# ruler.net
KiCad netlist of a schematic drawn in Altium Designer
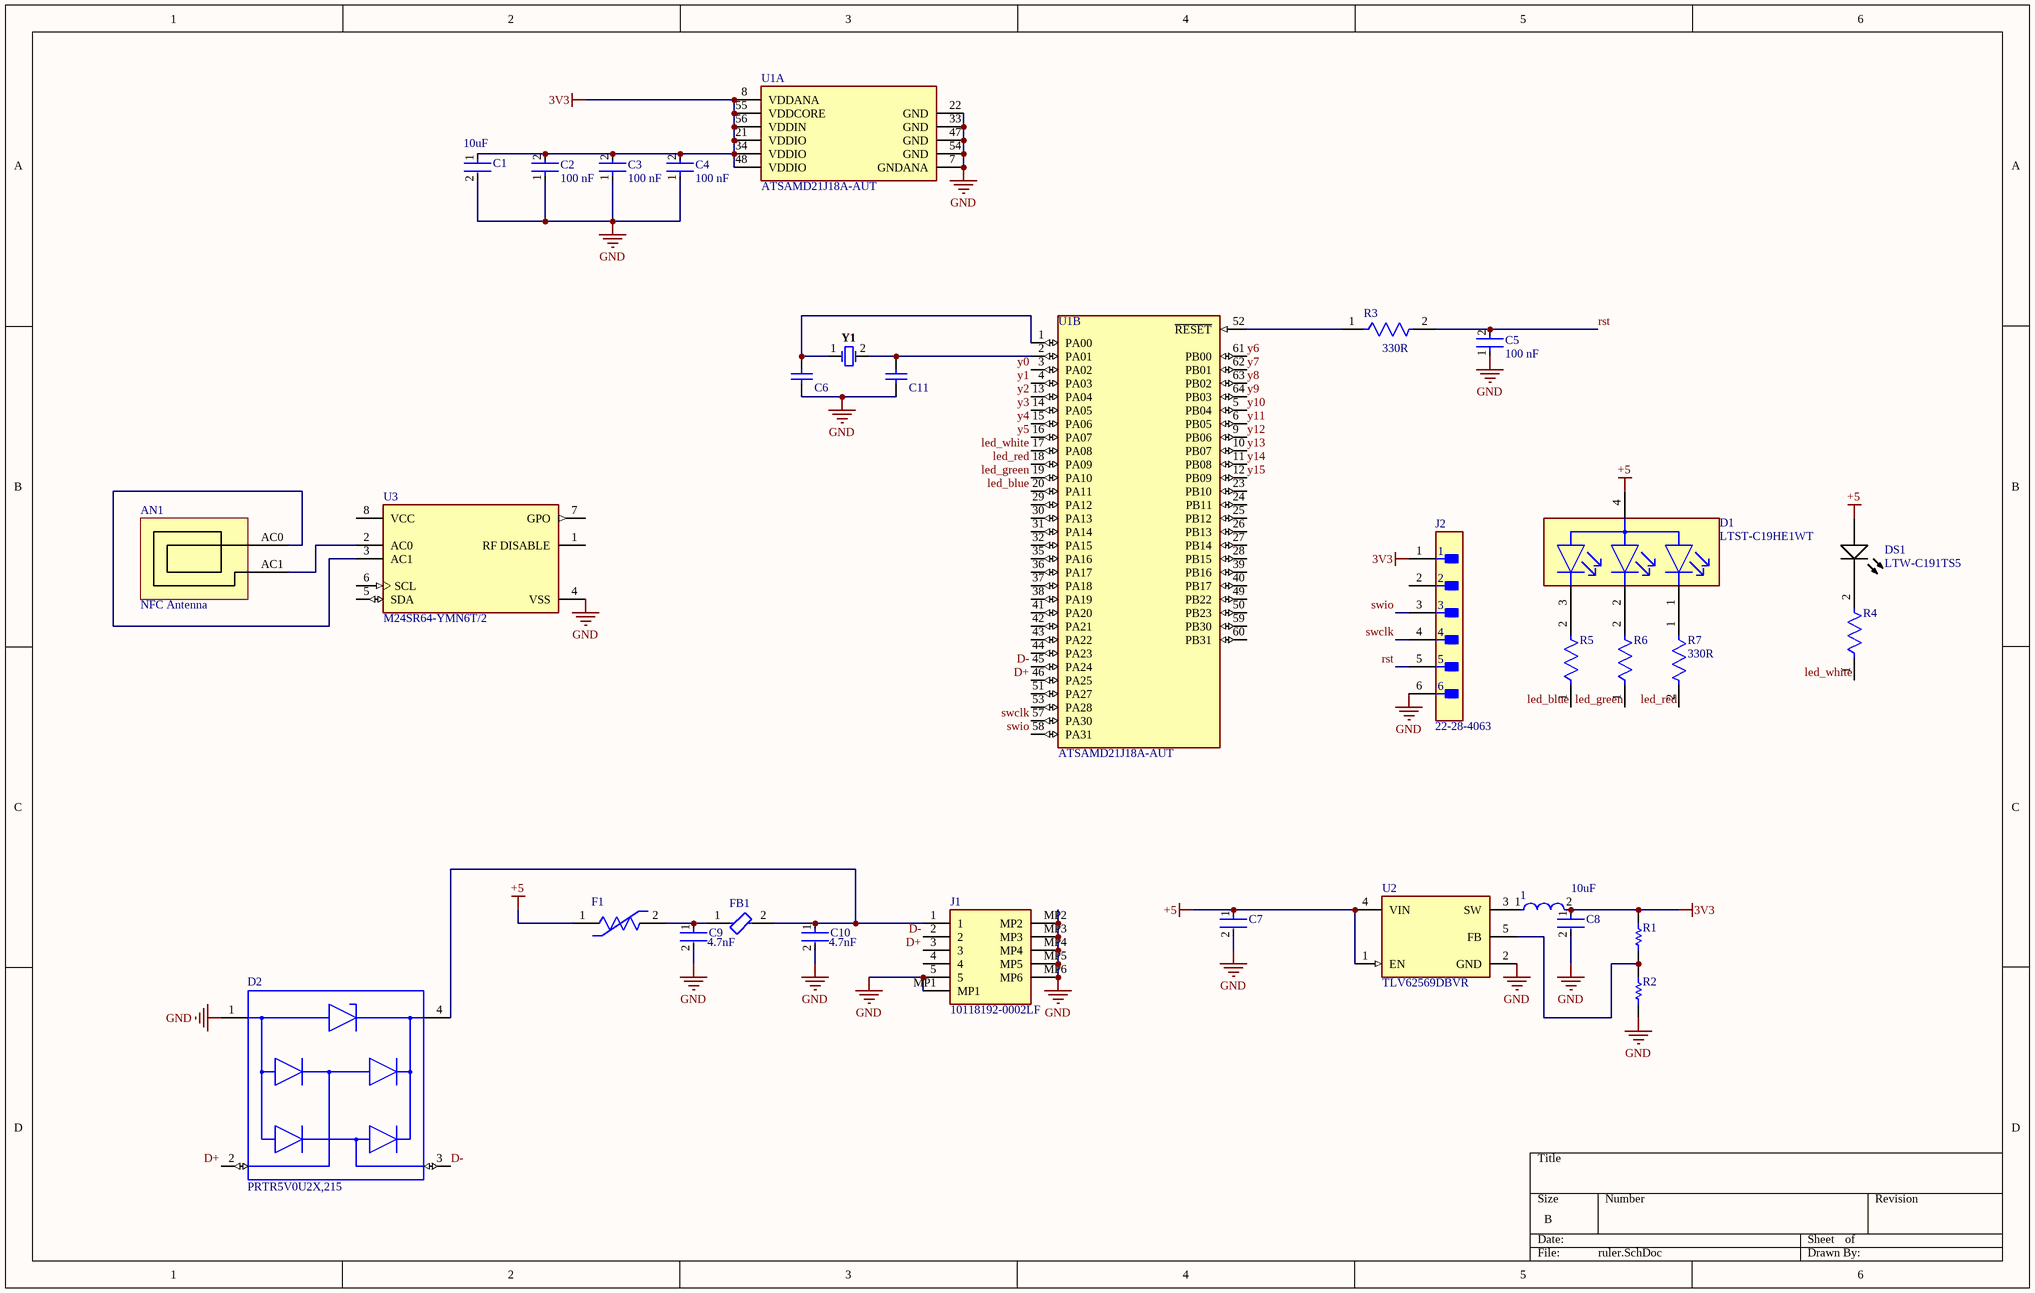
[diagram p0: ruler.SchDoc]

(export (version "E")
  (design (tool "Eeschema 10.0.6"))
  (components
    (comp (ref "1")
      (value "LQM2HPN2R2MG0L")
      (footprint "FP-LQM2HPN_G0-IPC_C")
      (description "Multilayer Type Inductor for Power Lines, 1008 (2520), 2.2μH, 20%, 0.1Ω, 1.3A")
      (fields (field (name "TOLERANCE") "20%") (field (name "MANUFACTURER") "Samsung"))
      (libsource (lib "Altium Content Vault") (part "725321dda6339637d4d059423bc1c3c"))
    )
    (comp (ref "AN1")
      (value "NFC Antenna")
      (footprint "NFC_Antenna")
      (description "L=5.51 uH, tuned for 13.56 MHz")
      (libsource (lib "NFC_Antenna") (part "NFC_Antenna"))
    )
    (comp (ref "C1")
      (value "CL10A106MP8NNNC")
      (footprint "FP-CL10-IPC_B")
      (description "Cap Ceramic 10uF 10V X5R ±20% Pad SMD 0603 +85°C T/R")
      (fields
        (field (name "CAPACITANCE") "10uF")
        (field (name "TOLERANCE") "20%")
        (field (name "LCSC PART NUMBER") "C85713")
      )
      (libsource (lib "Altium Content Vault") (part "b4654b650e69147ec39a6b967a45e02"))
    )
    (comp (ref "C2")
      (value "CC0603KRX7R9BB104")
      (footprint "FP-CC0603-DA-MFG")
      (description "CAP CER 0.1UF 50V X7R 0603")
      (fields
        (field (name "MANUFACTURER") "YAGEO")
        (field (name "VOLTAGE") "50 V")
        (field (name "CAPACITANCE") "100 nF")
      )
      (libsource (lib "Altium Content Vault") (part "11868f565c42a9108669ba33697ecf6"))
    )
    (comp (ref "C3")
      (value "CC0603KRX7R9BB104")
      (footprint "FP-CC0603-DA-MFG")
      (description "CAP CER 0.1UF 50V X7R 0603")
      (fields
        (field (name "MANUFACTURER") "YAGEO")
        (field (name "VOLTAGE") "50 V")
        (field (name "CAPACITANCE") "100 nF")
      )
      (libsource (lib "Altium Content Vault") (part "11868f565c42a9108669ba33697ecf6"))
    )
    (comp (ref "C4")
      (value "CC0603KRX7R9BB104")
      (footprint "FP-CC0603-DA-MFG")
      (description "CAP CER 0.1UF 50V X7R 0603")
      (fields
        (field (name "MANUFACTURER") "YAGEO")
        (field (name "VOLTAGE") "50 V")
        (field (name "CAPACITANCE") "100 nF")
      )
      (libsource (lib "Altium Content Vault") (part "11868f565c42a9108669ba33697ecf6"))
    )
    (comp (ref "C5")
      (value "CC0603KRX7R9BB104")
      (footprint "FP-CC0603-DA-MFG")
      (description "CAP CER 0.1UF 50V X7R 0603")
      (fields
        (field (name "MANUFACTURER") "YAGEO")
        (field (name "VOLTAGE") "50 V")
        (field (name "CAPACITANCE") "100 nF")
      )
      (libsource (lib "Altium Content Vault") (part "11868f565c42a9108669ba33697ecf6"))
    )
    (comp (ref "C6")
      (value "GRM1555C1E6R8CA01D")
      (footprint "CAPC1005X55X25NL05T10")
      (fields (field (name "MANUFACTURER") "Murata") (field (name "LCSC PART NUMBER") "C3877782"))
      (libsource (lib "Altium Content Vault") (part "CAP"))
    )
    (comp (ref "C7")
      (value "CL10A475KP8NNNC")
      (footprint "FP-CL10-IPC_C")
      (description "Cap Ceramic 4.7uF 10V X5R ±10% Pad SMD 0603 +85°C T/R")
      (fields (field (name "TOLERANCE") "10%") (field (name "LCSC PART NUMBER") "C1705"))
      (libsource (lib "Altium Content Vault") (part "b4654b650e69147ec39a6b967a45e02"))
    )
    (comp (ref "C8")
      (value "CL10A106MP8NNNC")
      (footprint "FP-CL10-IPC_B")
      (description "Cap Ceramic 10uF 10V X5R ±20% Pad SMD 0603 +85°C T/R")
      (fields
        (field (name "CAPACITANCE") "10uF")
        (field (name "TOLERANCE") "20%")
        (field (name "LCSC PART NUMBER") "C85713")
      )
      (libsource (lib "Altium Content Vault") (part "b4654b650e69147ec39a6b967a45e02"))
    )
    (comp (ref "C9")
      (value "GRM1885C1H472JA01D")
      (footprint "FP-GRM188-0_1-e0_2_0_5-MFG")
      (description "Chip Multilayer Ceramic Capacitors for General Purpose, 0603, 4700pF, C0G, 30ppm/°C, 5%, 50V")
      (fields
        (field (name "CAPACITANCE") "4.7nF")
        (field (name "TOLERANCE") "5%")
        (field (name "LCSC PART NUMBER") "C85980")
      )
      (libsource (lib "Altium Content Vault") (part "11868f565c42a9108669ba33697ecf6"))
    )
    (comp (ref "C10")
      (value "GRM1885C1H472JA01D")
      (footprint "FP-GRM188-0_1-e0_2_0_5-MFG")
      (description "Chip Multilayer Ceramic Capacitors for General Purpose, 0603, 4700pF, C0G, 30ppm/°C, 5%, 50V")
      (fields
        (field (name "CAPACITANCE") "4.7nF")
        (field (name "TOLERANCE") "5%")
        (field (name "LCSC PART NUMBER") "C85980")
      )
      (libsource (lib "Altium Content Vault") (part "11868f565c42a9108669ba33697ecf6"))
    )
    (comp (ref "C11")
      (value "GRM1555C1E6R8CA01D")
      (footprint "CAPC1005X55X25NL05T10")
      (fields (field (name "MANUFACTURER") "Murata") (field (name "LCSC PART NUMBER") "C3877782"))
      (libsource (lib "Altium Content Vault") (part "CAP"))
    )
    (comp (ref "D1")
      (value "LTST-C19HE1WT")
      (footprint "FP-LTST-C19HE1WT-MFG")
      (description "LED RGB DIFFUSED CHIP SMD")
      (fields (field (name "LCSC PART NUMBER") "C458749"))
      (libsource (lib "Altium Content Vault") (part "2c4e1fdd461916b293eda504ca5a2b6"))
    )
    (comp (ref "D2")
      (value "PRTR5V0U2X,215")
      (footprint "FP-SOT143B-MFG")
      (description "TVS DIODE 5.5V SOT143B")
      (fields (field (name "LCSC PART NUMBER") "C12333"))
      (libsource (lib "Altium Content Vault") (part "31e4fa1655694efd507c8a671e666ef"))
    )
    (comp (ref "DS1")
      (value "LTW-C191TS5")
      (footprint "LTST-LTW-C191TS5_V")
      (description "LED Uni-Color White, 70 mW, 20 mA, -20 to 80 degC, 2-Pin SMD, RoHS, Tape and Reel")
      (fields (field (name "TOLERANCE") "1%") (field (name "LCSC PART NUMBER") "C125123"))
      (libsource (lib "Altium Content Vault") (part "LED-WHITE-AK-2"))
    )
    (comp (ref "F1")
      (value "MF-MSMF050-2")
      (footprint "FP-MF-MSMF050-2-MFG")
      (description "PTC RESET FUSE 15V 500MA 1812")
      (fields
        (field (name "MANUFACTURER") "Bourns")
        (field (name "OCTOPART") "https://octopart.com/mf-msmf050-2-bourns-28047")
      )
      (libsource (lib "Altium Content Vault") (part "fc31388045fc42ab786d6d00b506e9f"))
    )
    (comp (ref "FB1")
      (value "BLM18PG471SN1D")
      (footprint "FP-BLM18-0_15-t0_8-MFG")
      (description "Chip Ferrite Bead, 0603, 470Ω @ 100MHz, 0.2Ω, 25%, 1A")
      (fields (field (name "TOLERANCE") "25%") (field (name "LCSC PART NUMBER") "C97853"))
      (libsource (lib "Altium Content Vault") (part "5f30dd21d616792df468990f7003faa"))
    )
    (comp (ref "J1")
      (value "10118192-0002LF")
      (footprint "SamacSys:101181920002LF")
      (description "Connector")
      (fields (field (name "LCSC PART NUMBER") "C2972784"))
      (libsource (lib "*") (part "10118192-0002LF"))
    )
    (comp (ref "J2")
      (value "22-28-4063")
      (footprint "FP-22-28-4063-MFG")
      (description "CONN HEADER VERT 6POS 2.54MM")
      (libsource (lib "Altium Content Vault") (part "f2cb566baf1c37ab5a3b8e90bbeafd6"))
    )
    (comp (ref "R1")
      (value "ERJ3EKF1913V")
      (footprint "RESC1608X55X30LL15T15")
      (fields
        (field (name "MANUFACTURER") "Panasonic")
        (field (name "PART NUMBER") "ERJ-3EKF1913V")
        (field (name "LCSC PART NUMBER") "C403050")
      )
      (libsource (lib "Altium Content Vault") (part "RES"))
    )
    (comp (ref "R2")
      (value "CRCW060342K2FKEA")
      (footprint "RESC1609X50X30ML10T20")
      (fields (field (name "MANUFACTURER") "Vishay Dale") (field (name "LCSC PART NUMBER") "C844563"))
      (libsource (lib "Altium Content Vault") (part "RES"))
    )
    (comp (ref "R3")
      (value "ERJ-PA3J331V")
      (footprint "FP-ERJPA3-MFG")
      (description "RES SMD 330 OHM 5% 1/4W 0603")
      (fields
        (field (name "TOLERANCE") "5%")
        (field (name "RESISTANCE") "330R")
        (field (name "LCSC PART NUMBER") "C441887")
      )
      (libsource (lib "Altium Content Vault") (part "1029c3af85768c4190bb7ad29bc67b5"))
    )
    (comp (ref "R4")
      (value "ERJ-3EKF2000V")
      (footprint "FP-ERJ3EK-IPC_C")
      (description "RES SMD 200 OHM 1% 1/10W 0603")
      (fields (field (name "TOLERANCE") "1%") (field (name "LCSC PART NUMBER") "C403056"))
      (libsource (lib "Altium Content Vault") (part "1029c3af85768c4190bb7ad29bc67b5"))
    )
    (comp (ref "R5")
      (value "ERJ-3EKF2000V")
      (footprint "FP-ERJ3EK-IPC_C")
      (description "RES SMD 200 OHM 1% 1/10W 0603")
      (fields (field (name "TOLERANCE") "1%") (field (name "LCSC PART NUMBER") "C403056"))
      (libsource (lib "Altium Content Vault") (part "1029c3af85768c4190bb7ad29bc67b5"))
    )
    (comp (ref "R6")
      (value "ERJ-3EKF2000V")
      (footprint "FP-ERJ3EK-IPC_C")
      (description "RES SMD 200 OHM 1% 1/10W 0603")
      (fields (field (name "TOLERANCE") "1%") (field (name "LCSC PART NUMBER") "C403056"))
      (libsource (lib "Altium Content Vault") (part "1029c3af85768c4190bb7ad29bc67b5"))
    )
    (comp (ref "R7")
      (value "ERJ-PA3J331V")
      (footprint "FP-ERJPA3-MFG")
      (description "RES SMD 330 OHM 5% 1/4W 0603")
      (fields
        (field (name "TOLERANCE") "5%")
        (field (name "RESISTANCE") "330R")
        (field (name "LCSC PART NUMBER") "C441887")
      )
      (libsource (lib "Altium Content Vault") (part "1029c3af85768c4190bb7ad29bc67b5"))
    )
    (comp (ref "U1")
      (value "ATSAMD21J18A-AUT")
      (footprint "FP-MF-IPC_C")
      (description "IC MCU 32BIT 256KB FLASH 64TQFP")
      (fields (field (name "LCSC PART NUMBER") "C515529"))
      (libsource (lib "Altium Content Vault") (part "65ab6eae36ab959888c09c9014c00ce"))
    )
    (comp (ref "U2")
      (value "TLV62569DBVR")
      (footprint "FP-DBV0005A-MFG")
      (description "IC REG BUCK ADJ 2A SOT23-5")
      (fields
        (field (name "MANUFACTURER") "Samsung")
        (field (name "MANUFACTURER PART NUMBER") "CL10A106KP8NNNC")
      )
      (libsource (lib "Altium Content Vault") (part "f8671745ee5fb9a493b385c735b730b"))
    )
    (comp (ref "U3")
      (value "M24SR64-YMN6T/2")
      (footprint "FP-SO-A-MFG")
      (description "IC RFID TRANSP 13.56MHZ 8SO")
      (fields (field (name "LCSC PART NUMBER") "C222221"))
      (libsource (lib "Altium Content Vault") (part "53a1da70939e62a8eb501fa3a9e7f19"))
    )
    (comp (ref "Y1")
      (value "CM315D32768DZFT")
      (footprint "CMHT-CM315D-2_V")
      (description "Turning Fork Crystal Unit, 32.768 KHz, -40 to 85 degC, 2-Pin SMD, RoHS, Tape and Reel")
      (fields
        (field (name "MANUFACTURER") "Citizen Micro HumanTech")
        (field (name "LCSC PART NUMBER") "C182057")
      )
      (libsource (lib "Altium Content Vault") (part "XTAL-1-2-2"))
    )
  )
  (nets
    (net (code "1") (name "+5") (class "Default")
      (node (ref "C7") (pin "1") (pinfunction "1_1") (pintype "passive"))
      (node (ref "D1") (pin "4") (pinfunction "A_4") (pintype "passive"))
      (node (ref "DS1") (pin "1") (pinfunction "A_1") (pintype "passive"))
      (node (ref "F1") (pin "1") (pinfunction "1_1") (pintype "passive"))
      (node (ref "U2") (pin "1") (pinfunction "EN_1") (pintype "input"))
      (node (ref "U2") (pin "4") (pinfunction "VIN_4") (pintype "power_in"))
    )
    (net (code "2") (name "/D+") (class "Default")
      (node (ref "D2") (pin "2") (pinfunction "I/O_1_2") (pintype "bidirectional"))
      (node (ref "J1") (pin "3") (pinfunction "3_3") (pintype "passive"))
      (node (ref "U1") (pin "46") (pinfunction "PA25_46") (pintype "bidirectional"))
    )
    (net (code "3") (name "/D-") (class "Default")
      (node (ref "D2") (pin "3") (pinfunction "I/O_2_3") (pintype "bidirectional"))
      (node (ref "J1") (pin "2") (pinfunction "2_2") (pintype "passive"))
      (node (ref "U1") (pin "45") (pinfunction "PA24_45") (pintype "bidirectional"))
    )
    (net (code "4") (name "/led_blue") (class "Default")
      (node (ref "R5") (pin "1") (pinfunction "1_1") (pintype "passive"))
      (node (ref "U1") (pin "20") (pinfunction "PA11_20") (pintype "bidirectional"))
    )
    (net (code "5") (name "/led_green") (class "Default")
      (node (ref "R6") (pin "1") (pinfunction "1_1") (pintype "passive"))
      (node (ref "U1") (pin "19") (pinfunction "PA10_19") (pintype "bidirectional"))
    )
    (net (code "6") (name "/led_red") (class "Default")
      (node (ref "R7") (pin "2") (pinfunction "2_2") (pintype "passive"))
      (node (ref "U1") (pin "18") (pinfunction "PA09_18") (pintype "bidirectional"))
    )
    (net (code "7") (name "/led_white") (class "Default")
      (node (ref "R4") (pin "1") (pinfunction "1_1") (pintype "passive"))
      (node (ref "U1") (pin "17") (pinfunction "PA08_17") (pintype "bidirectional"))
    )
    (net (code "8") (name "/rst") (class "Default")
      (node (ref "C5") (pin "2") (pinfunction "2_2") (pintype "passive"))
      (node (ref "J2") (pin "5") (pinfunction "5_5") (pintype "passive"))
      (node (ref "R3") (pin "2") (pinfunction "2_2") (pintype "passive"))
    )
    (net (code "9") (name "/swclk") (class "Default")
      (node (ref "J2") (pin "4") (pinfunction "4_4") (pintype "passive"))
      (node (ref "U1") (pin "57") (pinfunction "PA30_57") (pintype "bidirectional"))
    )
    (net (code "10") (name "/swio") (class "Default")
      (node (ref "J2") (pin "3") (pinfunction "3_3") (pintype "passive"))
      (node (ref "U1") (pin "58") (pinfunction "PA31_58") (pintype "bidirectional"))
    )
    (net (code "11") (name "/y0") (class "Default")
      (node (ref "U1") (pin "3") (pinfunction "PA02_3") (pintype "bidirectional"))
    )
    (net (code "12") (name "/y1") (class "Default")
      (node (ref "U1") (pin "4") (pinfunction "PA03_4") (pintype "bidirectional"))
    )
    (net (code "13") (name "/y2") (class "Default")
      (node (ref "U1") (pin "13") (pinfunction "PA04_13") (pintype "bidirectional"))
    )
    (net (code "14") (name "/y3") (class "Default")
      (node (ref "U1") (pin "14") (pinfunction "PA05_14") (pintype "bidirectional"))
    )
    (net (code "15") (name "/y4") (class "Default")
      (node (ref "U1") (pin "15") (pinfunction "PA06_15") (pintype "bidirectional"))
    )
    (net (code "16") (name "/y5") (class "Default")
      (node (ref "U1") (pin "16") (pinfunction "PA07_16") (pintype "bidirectional"))
    )
    (net (code "17") (name "/y6") (class "Default")
      (node (ref "U1") (pin "61") (pinfunction "PB00_61") (pintype "bidirectional"))
    )
    (net (code "18") (name "/y7") (class "Default")
      (node (ref "U1") (pin "62") (pinfunction "PB01_62") (pintype "bidirectional"))
    )
    (net (code "19") (name "/y8") (class "Default")
      (node (ref "U1") (pin "63") (pinfunction "PB02_63") (pintype "bidirectional"))
    )
    (net (code "20") (name "/y9") (class "Default")
      (node (ref "U1") (pin "64") (pinfunction "PB03_64") (pintype "bidirectional"))
    )
    (net (code "21") (name "/y10") (class "Default")
      (node (ref "U1") (pin "5") (pinfunction "PB04_5") (pintype "bidirectional"))
    )
    (net (code "22") (name "/y11") (class "Default")
      (node (ref "U1") (pin "6") (pinfunction "PB05_6") (pintype "bidirectional"))
    )
    (net (code "23") (name "/y12") (class "Default")
      (node (ref "U1") (pin "9") (pinfunction "PB06_9") (pintype "bidirectional"))
    )
    (net (code "24") (name "/y13") (class "Default")
      (node (ref "U1") (pin "10") (pinfunction "PB07_10") (pintype "bidirectional"))
    )
    (net (code "25") (name "/y14") (class "Default")
      (node (ref "U1") (pin "11") (pinfunction "PB08_11") (pintype "bidirectional"))
    )
    (net (code "26") (name "/y15") (class "Default")
      (node (ref "U1") (pin "12") (pinfunction "PB09_12") (pintype "bidirectional"))
    )
    (net (code "27") (name "3V3") (class "Default")
      (node (ref "1") (pin "2") (pinfunction "2_2") (pintype "passive"))
      (node (ref "C1") (pin "1") (pinfunction "1_1") (pintype "passive"))
      (node (ref "C2") (pin "2") (pinfunction "2_2") (pintype "passive"))
      (node (ref "C3") (pin "2") (pinfunction "2_2") (pintype "passive"))
      (node (ref "C4") (pin "2") (pinfunction "2_2") (pintype "passive"))
      (node (ref "C8") (pin "1") (pinfunction "1_1") (pintype "passive"))
      (node (ref "J2") (pin "1") (pinfunction "1_1") (pintype "passive"))
      (node (ref "R1") (pin "2") (pinfunction "2_2") (pintype "passive"))
      (node (ref "U1") (pin "21") (pinfunction "VDDIO_21") (pintype "power_in"))
      (node (ref "U1") (pin "34") (pinfunction "VDDIO_34") (pintype "power_in"))
      (node (ref "U1") (pin "48") (pinfunction "VDDIO_48") (pintype "power_in"))
      (node (ref "U1") (pin "55") (pinfunction "VDDCORE_55") (pintype "power_in"))
      (node (ref "U1") (pin "56") (pinfunction "VDDIN_56") (pintype "power_in"))
      (node (ref "U1") (pin "8") (pinfunction "VDDANA_8") (pintype "power_in"))
    )
    (net (code "28") (name "GND") (class "Default")
      (node (ref "C1") (pin "2") (pinfunction "2_2") (pintype "passive"))
      (node (ref "C10") (pin "2") (pinfunction "2_2") (pintype "passive"))
      (node (ref "C11") (pin "1") (pinfunction "1_1") (pintype "passive"))
      (node (ref "C2") (pin "1") (pinfunction "1_1") (pintype "passive"))
      (node (ref "C3") (pin "1") (pinfunction "1_1") (pintype "passive"))
      (node (ref "C4") (pin "1") (pinfunction "1_1") (pintype "passive"))
      (node (ref "C5") (pin "1") (pinfunction "1_1") (pintype "passive"))
      (node (ref "C6") (pin "1") (pinfunction "1_1") (pintype "passive"))
      (node (ref "C7") (pin "2") (pinfunction "2_2") (pintype "passive"))
      (node (ref "C8") (pin "2") (pinfunction "2_2") (pintype "passive"))
      (node (ref "C9") (pin "2") (pinfunction "2_2") (pintype "passive"))
      (node (ref "D2") (pin "1") (pinfunction "GND_1") (pintype "power_in"))
      (node (ref "J1") (pin "5") (pinfunction "5_5") (pintype "passive"))
      (node (ref "J1") (pin "MP1") (pinfunction "MP1_MP1") (pintype "passive"))
      (node (ref "J1") (pin "MP2") (pinfunction "MP2_MP2") (pintype "passive"))
      (node (ref "J1") (pin "MP3") (pinfunction "MP3_MP3") (pintype "passive"))
      (node (ref "J1") (pin "MP4") (pinfunction "MP4_MP4") (pintype "passive"))
      (node (ref "J1") (pin "MP5") (pinfunction "MP5_MP5") (pintype "passive"))
      (node (ref "J1") (pin "MP6") (pinfunction "MP6_MP6") (pintype "passive"))
      (node (ref "J2") (pin "6") (pinfunction "6_6") (pintype "passive"))
      (node (ref "R2") (pin "1") (pinfunction "1_1") (pintype "passive"))
      (node (ref "U1") (pin "22") (pinfunction "GND_22") (pintype "power_in"))
      (node (ref "U1") (pin "33") (pinfunction "GND_33") (pintype "power_in"))
      (node (ref "U1") (pin "47") (pinfunction "GND_47") (pintype "power_in"))
      (node (ref "U1") (pin "54") (pinfunction "GND_54") (pintype "power_in"))
      (node (ref "U1") (pin "7") (pinfunction "GNDANA_7") (pintype "power_in"))
      (node (ref "U2") (pin "2") (pinfunction "GND_2") (pintype "power_in"))
      (node (ref "U3") (pin "4") (pinfunction "VSS_4") (pintype "power_in"))
    )
    (net (code "29") (name "Net-(C9-Pad1)") (class "Default")
      (node (ref "C9") (pin "1") (pinfunction "1_1") (pintype "passive"))
      (node (ref "F1") (pin "2") (pinfunction "2_2") (pintype "passive"))
      (node (ref "FB1") (pin "1") (pinfunction "1_1") (pintype "passive"))
    )
    (net (code "30") (name "Net-(D1-BLUE_C)") (class "Default")
      (node (ref "D1") (pin "3") (pinfunction "BLUE_C_3") (pintype "passive"))
      (node (ref "R5") (pin "2") (pinfunction "2_2") (pintype "passive"))
    )
    (net (code "31") (name "Net-(D1-GREEN_C)") (class "Default")
      (node (ref "D1") (pin "2") (pinfunction "GREEN_C_2") (pintype "passive"))
      (node (ref "R6") (pin "2") (pinfunction "2_2") (pintype "passive"))
    )
    (net (code "32") (name "Net-(D1-RED_C)") (class "Default")
      (node (ref "D1") (pin "1") (pinfunction "RED_C_1") (pintype "passive"))
      (node (ref "R7") (pin "1") (pinfunction "1_1") (pintype "passive"))
    )
    (net (code "33") (name "Net-(D2-VCC)") (class "Default")
      (node (ref "C10") (pin "1") (pinfunction "1_1") (pintype "passive"))
      (node (ref "D2") (pin "4") (pinfunction "VCC_4") (pintype "power_in"))
      (node (ref "FB1") (pin "2") (pinfunction "2_2") (pintype "passive"))
      (node (ref "J1") (pin "1") (pinfunction "1_1") (pintype "passive"))
    )
    (net (code "34") (name "Net-(DS1-K)") (class "Default")
      (node (ref "DS1") (pin "2") (pinfunction "K_2") (pintype "passive"))
      (node (ref "R4") (pin "2") (pinfunction "2_2") (pintype "passive"))
    )
    (net (code "35") (name "Net-(U1B-PA00)") (class "Default")
      (node (ref "C6") (pin "2") (pinfunction "2_2") (pintype "passive"))
      (node (ref "U1") (pin "1") (pinfunction "PA00_1") (pintype "bidirectional"))
      (node (ref "Y1") (pin "1") (pinfunction "1_1") (pintype "passive"))
    )
    (net (code "36") (name "Net-(U1B-PA01)") (class "Default")
      (node (ref "C11") (pin "2") (pinfunction "2_2") (pintype "passive"))
      (node (ref "U1") (pin "2") (pinfunction "PA01_2") (pintype "bidirectional"))
      (node (ref "Y1") (pin "2") (pinfunction "2_2") (pintype "passive"))
    )
    (net (code "37") (name "Net-(U1B-~{RESET})") (class "Default")
      (node (ref "R3") (pin "1") (pinfunction "1_1") (pintype "passive"))
      (node (ref "U1") (pin "52") (pinfunction "~{RESET}_52") (pintype "input"))
    )
    (net (code "38") (name "Net-(U2-FB)") (class "Default")
      (node (ref "R1") (pin "1") (pinfunction "1_1") (pintype "passive"))
      (node (ref "R2") (pin "2") (pinfunction "2_2") (pintype "passive"))
      (node (ref "U2") (pin "5") (pinfunction "FB_5") (pintype "passive"))
    )
    (net (code "39") (name "Net-(U2-SW)") (class "Default")
      (node (ref "1") (pin "1") (pinfunction "1_1") (pintype "passive"))
      (node (ref "U2") (pin "3") (pinfunction "SW_3") (pintype "power_in"))
    )
    (net (code "40") (name "Net-(U3-AC0)") (class "Default")
      (node (ref "AN1") (pin "AC1") (pintype "passive"))
      (node (ref "U3") (pin "2") (pinfunction "AC0_2") (pintype "passive"))
    )
    (net (code "41") (name "Net-(U3-AC1)") (class "Default")
      (node (ref "AN1") (pin "AC0") (pintype "passive"))
      (node (ref "U3") (pin "3") (pinfunction "AC1_3") (pintype "passive"))
    )
    (net (code "42") (name "unconnected-(J1-Pad4)") (class "Default")
      (node (ref "J1") (pin "4") (pinfunction "4_4") (pintype "passive"))
    )
    (net (code "43") (name "unconnected-(J2-Pad2)") (class "Default")
      (node (ref "J2") (pin "2") (pinfunction "2_2") (pintype "passive"))
    )
    (net (code "44") (name "unconnected-(U1B-PA12-Pad29)") (class "Default")
      (node (ref "U1") (pin "29") (pinfunction "PA12_29") (pintype "bidirectional"))
    )
    (net (code "45") (name "unconnected-(U1B-PA13-Pad30)") (class "Default")
      (node (ref "U1") (pin "30") (pinfunction "PA13_30") (pintype "bidirectional"))
    )
    (net (code "46") (name "unconnected-(U1B-PA14-Pad31)") (class "Default")
      (node (ref "U1") (pin "31") (pinfunction "PA14_31") (pintype "bidirectional"))
    )
    (net (code "47") (name "unconnected-(U1B-PA15-Pad32)") (class "Default")
      (node (ref "U1") (pin "32") (pinfunction "PA15_32") (pintype "bidirectional"))
    )
    (net (code "48") (name "unconnected-(U1B-PA16-Pad35)") (class "Default")
      (node (ref "U1") (pin "35") (pinfunction "PA16_35") (pintype "bidirectional"))
    )
    (net (code "49") (name "unconnected-(U1B-PA17-Pad36)") (class "Default")
      (node (ref "U1") (pin "36") (pinfunction "PA17_36") (pintype "bidirectional"))
    )
    (net (code "50") (name "unconnected-(U1B-PA18-Pad37)") (class "Default")
      (node (ref "U1") (pin "37") (pinfunction "PA18_37") (pintype "bidirectional"))
    )
    (net (code "51") (name "unconnected-(U1B-PA19-Pad38)") (class "Default")
      (node (ref "U1") (pin "38") (pinfunction "PA19_38") (pintype "bidirectional"))
    )
    (net (code "52") (name "unconnected-(U1B-PA20-Pad41)") (class "Default")
      (node (ref "U1") (pin "41") (pinfunction "PA20_41") (pintype "bidirectional"))
    )
    (net (code "53") (name "unconnected-(U1B-PA21-Pad42)") (class "Default")
      (node (ref "U1") (pin "42") (pinfunction "PA21_42") (pintype "bidirectional"))
    )
    (net (code "54") (name "unconnected-(U1B-PA22-Pad43)") (class "Default")
      (node (ref "U1") (pin "43") (pinfunction "PA22_43") (pintype "bidirectional"))
    )
    (net (code "55") (name "unconnected-(U1B-PA23-Pad44)") (class "Default")
      (node (ref "U1") (pin "44") (pinfunction "PA23_44") (pintype "bidirectional"))
    )
    (net (code "56") (name "unconnected-(U1B-PA27-Pad51)") (class "Default")
      (node (ref "U1") (pin "51") (pinfunction "PA27_51") (pintype "bidirectional"))
    )
    (net (code "57") (name "unconnected-(U1B-PA28-Pad53)") (class "Default")
      (node (ref "U1") (pin "53") (pinfunction "PA28_53") (pintype "bidirectional"))
    )
    (net (code "58") (name "unconnected-(U1B-PB10-Pad23)") (class "Default")
      (node (ref "U1") (pin "23") (pinfunction "PB10_23") (pintype "bidirectional"))
    )
    (net (code "59") (name "unconnected-(U1B-PB11-Pad24)") (class "Default")
      (node (ref "U1") (pin "24") (pinfunction "PB11_24") (pintype "bidirectional"))
    )
    (net (code "60") (name "unconnected-(U1B-PB12-Pad25)") (class "Default")
      (node (ref "U1") (pin "25") (pinfunction "PB12_25") (pintype "bidirectional"))
    )
    (net (code "61") (name "unconnected-(U1B-PB13-Pad26)") (class "Default")
      (node (ref "U1") (pin "26") (pinfunction "PB13_26") (pintype "bidirectional"))
    )
    (net (code "62") (name "unconnected-(U1B-PB14-Pad27)") (class "Default")
      (node (ref "U1") (pin "27") (pinfunction "PB14_27") (pintype "bidirectional"))
    )
    (net (code "63") (name "unconnected-(U1B-PB15-Pad28)") (class "Default")
      (node (ref "U1") (pin "28") (pinfunction "PB15_28") (pintype "bidirectional"))
    )
    (net (code "64") (name "unconnected-(U1B-PB16-Pad39)") (class "Default")
      (node (ref "U1") (pin "39") (pinfunction "PB16_39") (pintype "bidirectional"))
    )
    (net (code "65") (name "unconnected-(U1B-PB17-Pad40)") (class "Default")
      (node (ref "U1") (pin "40") (pinfunction "PB17_40") (pintype "bidirectional"))
    )
    (net (code "66") (name "unconnected-(U1B-PB22-Pad49)") (class "Default")
      (node (ref "U1") (pin "49") (pinfunction "PB22_49") (pintype "bidirectional"))
    )
    (net (code "67") (name "unconnected-(U1B-PB23-Pad50)") (class "Default")
      (node (ref "U1") (pin "50") (pinfunction "PB23_50") (pintype "bidirectional"))
    )
    (net (code "68") (name "unconnected-(U1B-PB30-Pad59)") (class "Default")
      (node (ref "U1") (pin "59") (pinfunction "PB30_59") (pintype "bidirectional"))
    )
    (net (code "69") (name "unconnected-(U1B-PB31-Pad60)") (class "Default")
      (node (ref "U1") (pin "60") (pinfunction "PB31_60") (pintype "bidirectional"))
    )
    (net (code "70") (name "unconnected-(U3-GPO-Pad7)") (class "Default")
      (node (ref "U3") (pin "7") (pinfunction "GPO_7") (pintype "output"))
    )
    (net (code "71") (name "unconnected-(U3-RF_DISABLE-Pad1)") (class "Default")
      (node (ref "U3") (pin "1") (pinfunction "RF_DISABLE_1") (pintype "passive"))
    )
    (net (code "72") (name "unconnected-(U3-SCL-Pad6)") (class "Default")
      (node (ref "U3") (pin "6") (pinfunction "SCL_6") (pintype "input"))
    )
    (net (code "73") (name "unconnected-(U3-SDA-Pad5)") (class "Default")
      (node (ref "U3") (pin "5") (pinfunction "SDA_5") (pintype "bidirectional"))
    )
    (net (code "74") (name "unconnected-(U3-VCC-Pad8)") (class "Default")
      (node (ref "U3") (pin "8") (pinfunction "VCC_8") (pintype "power_in"))
    )
  )
)
